# Sheet1_PCI_mez.net
KiCad netlist of a schematic drawn in Altium Designer
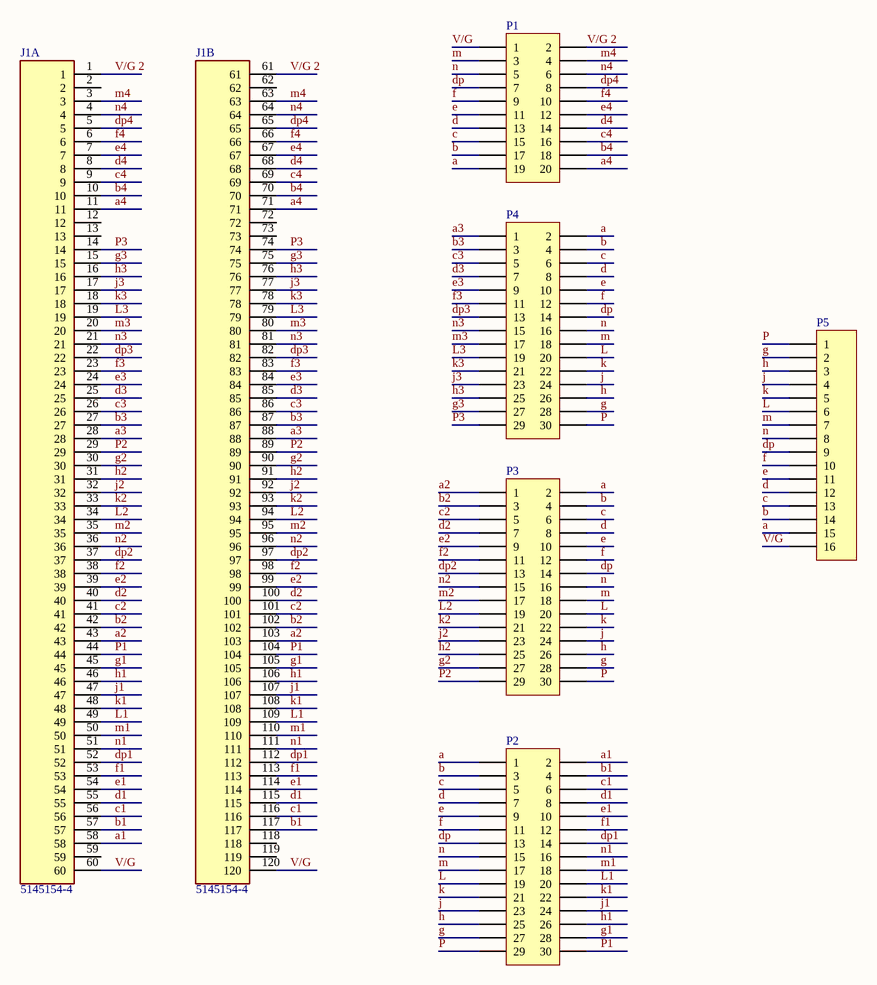
[diagram p0: Sheet1_PCI_mez.SchDoc]

(export (version "E")
  (design (tool "Eeschema 10.0.6"))
  (components
    (comp (ref "J1")
      (value "5145154-4")
      (footprint "TE_5145154-4")
      (description "Conn, Card Edge, Thermoplastic, White, 60 Dual Pos., Gold Cont., PCI ¦ TE Connectivity 5145154-4")
      (fields (field (name "MF") "TE Connectivity"))
      (libsource (lib "5145154-4") (part "5145154-4"))
    )
    (comp (ref "P1")
      (value "Header 10X2")
      (footprint "HDR2X10")
      (description "Header, 10-Pin, Dual row")
      (fields (field (name "PUBLISHER") "Altium Limited"))
      (libsource (lib "Miscellaneous Connectors") (part "Header 10X2"))
    )
    (comp (ref "P2")
      (value "Header 15X2")
      (footprint "HDR2X15")
      (description "Header, 15-Pin, Dual row")
      (fields (field (name "PUBLISHER") "Altium Limited"))
      (libsource (lib "Miscellaneous Connectors") (part "Header 15X2"))
    )
    (comp (ref "P3")
      (value "Header 15X2")
      (footprint "HDR2X15")
      (description "Header, 15-Pin, Dual row")
      (fields (field (name "PUBLISHER") "Altium Limited"))
      (libsource (lib "Miscellaneous Connectors") (part "Header 15X2"))
    )
    (comp (ref "P4")
      (value "Header 15X2")
      (footprint "HDR2X15")
      (description "Header, 15-Pin, Dual row")
      (fields (field (name "PUBLISHER") "Altium Limited"))
      (libsource (lib "Miscellaneous Connectors") (part "Header 15X2"))
    )
    (comp (ref "P5")
      (value "Header 16")
      (footprint "HDR1X16")
      (description "Header, 16-Pin")
      (fields (field (name "PUBLISHER") "Altium Limited"))
      (libsource (lib "Miscellaneous Connectors") (part "Header 16"))
    )
  )
  (nets
    (net (code "1") (name "/L") (class "Default")
      (node (ref "P2") (pin "19") (pinfunction "19_19") (pintype "passive"))
      (node (ref "P3") (pin "20") (pinfunction "20_20") (pintype "passive"))
      (node (ref "P4") (pin "20") (pinfunction "20_20") (pintype "passive"))
      (node (ref "P5") (pin "6") (pinfunction "6_6") (pintype "passive"))
    )
    (net (code "2") (name "/L1") (class "Default")
      (node (ref "J1") (pin "109") (pinfunction "109_109") (pintype "passive"))
      (node (ref "J1") (pin "49") (pinfunction "49_49") (pintype "passive"))
      (node (ref "P2") (pin "20") (pinfunction "20_20") (pintype "passive"))
    )
    (net (code "3") (name "/L2") (class "Default")
      (node (ref "J1") (pin "34") (pinfunction "34_34") (pintype "passive"))
      (node (ref "J1") (pin "94") (pinfunction "94_94") (pintype "passive"))
      (node (ref "P3") (pin "19") (pinfunction "19_19") (pintype "passive"))
    )
    (net (code "4") (name "/L3") (class "Default")
      (node (ref "J1") (pin "19") (pinfunction "19_19") (pintype "passive"))
      (node (ref "J1") (pin "79") (pinfunction "79_79") (pintype "passive"))
      (node (ref "P4") (pin "19") (pinfunction "19_19") (pintype "passive"))
    )
    (net (code "5") (name "/P") (class "Default")
      (node (ref "P2") (pin "29") (pinfunction "29_29") (pintype "passive"))
      (node (ref "P3") (pin "30") (pinfunction "30_30") (pintype "passive"))
      (node (ref "P4") (pin "30") (pinfunction "30_30") (pintype "passive"))
      (node (ref "P5") (pin "1") (pinfunction "1_1") (pintype "passive"))
    )
    (net (code "6") (name "/P1") (class "Default")
      (node (ref "J1") (pin "104") (pinfunction "104_104") (pintype "passive"))
      (node (ref "J1") (pin "44") (pinfunction "44_44") (pintype "passive"))
      (node (ref "P2") (pin "30") (pinfunction "30_30") (pintype "passive"))
    )
    (net (code "7") (name "/P2") (class "Default")
      (node (ref "J1") (pin "29") (pinfunction "29_29") (pintype "passive"))
      (node (ref "J1") (pin "89") (pinfunction "89_89") (pintype "passive"))
      (node (ref "P3") (pin "29") (pinfunction "29_29") (pintype "passive"))
    )
    (net (code "8") (name "/P3") (class "Default")
      (node (ref "J1") (pin "14") (pinfunction "14_14") (pintype "passive"))
      (node (ref "J1") (pin "74") (pinfunction "74_74") (pintype "passive"))
      (node (ref "P4") (pin "29") (pinfunction "29_29") (pintype "passive"))
    )
    (net (code "9") (name "/V{slash}G") (class "Default")
      (node (ref "J1") (pin "120") (pinfunction "120_120") (pintype "passive"))
      (node (ref "J1") (pin "60") (pinfunction "60_60") (pintype "passive"))
      (node (ref "P1") (pin "1") (pinfunction "1_1") (pintype "passive"))
      (node (ref "P5") (pin "16") (pinfunction "16_16") (pintype "passive"))
    )
    (net (code "10") (name "/V{slash}G 2") (class "Default")
      (node (ref "J1") (pin "1") (pinfunction "1_1") (pintype "passive"))
      (node (ref "J1") (pin "61") (pinfunction "61_61") (pintype "passive"))
      (node (ref "P1") (pin "2") (pinfunction "2_2") (pintype "passive"))
    )
    (net (code "11") (name "/a") (class "Default")
      (node (ref "P1") (pin "19") (pinfunction "19_19") (pintype "passive"))
      (node (ref "P2") (pin "1") (pinfunction "1_1") (pintype "passive"))
      (node (ref "P3") (pin "2") (pinfunction "2_2") (pintype "passive"))
      (node (ref "P4") (pin "2") (pinfunction "2_2") (pintype "passive"))
      (node (ref "P5") (pin "15") (pinfunction "15_15") (pintype "passive"))
    )
    (net (code "12") (name "/a1") (class "Default")
      (node (ref "J1") (pin "58") (pinfunction "58_58") (pintype "passive"))
      (node (ref "P2") (pin "2") (pinfunction "2_2") (pintype "passive"))
    )
    (net (code "13") (name "/a2") (class "Default")
      (node (ref "J1") (pin "103") (pinfunction "103_103") (pintype "passive"))
      (node (ref "J1") (pin "43") (pinfunction "43_43") (pintype "passive"))
      (node (ref "P3") (pin "1") (pinfunction "1_1") (pintype "passive"))
    )
    (net (code "14") (name "/a3") (class "Default")
      (node (ref "J1") (pin "28") (pinfunction "28_28") (pintype "passive"))
      (node (ref "J1") (pin "88") (pinfunction "88_88") (pintype "passive"))
      (node (ref "P4") (pin "1") (pinfunction "1_1") (pintype "passive"))
    )
    (net (code "15") (name "/a4") (class "Default")
      (node (ref "J1") (pin "11") (pinfunction "11_11") (pintype "passive"))
      (node (ref "J1") (pin "71") (pinfunction "71_71") (pintype "passive"))
      (node (ref "P1") (pin "20") (pinfunction "20_20") (pintype "passive"))
    )
    (net (code "16") (name "/b") (class "Default")
      (node (ref "P1") (pin "17") (pinfunction "17_17") (pintype "passive"))
      (node (ref "P2") (pin "3") (pinfunction "3_3") (pintype "passive"))
      (node (ref "P3") (pin "4") (pinfunction "4_4") (pintype "passive"))
      (node (ref "P4") (pin "4") (pinfunction "4_4") (pintype "passive"))
      (node (ref "P5") (pin "14") (pinfunction "14_14") (pintype "passive"))
    )
    (net (code "17") (name "/b1") (class "Default")
      (node (ref "J1") (pin "117") (pinfunction "117_117") (pintype "passive"))
      (node (ref "J1") (pin "57") (pinfunction "57_57") (pintype "passive"))
      (node (ref "P2") (pin "4") (pinfunction "4_4") (pintype "passive"))
    )
    (net (code "18") (name "/b2") (class "Default")
      (node (ref "J1") (pin "102") (pinfunction "102_102") (pintype "passive"))
      (node (ref "J1") (pin "42") (pinfunction "42_42") (pintype "passive"))
      (node (ref "P3") (pin "3") (pinfunction "3_3") (pintype "passive"))
    )
    (net (code "19") (name "/b3") (class "Default")
      (node (ref "J1") (pin "27") (pinfunction "27_27") (pintype "passive"))
      (node (ref "J1") (pin "87") (pinfunction "87_87") (pintype "passive"))
      (node (ref "P4") (pin "3") (pinfunction "3_3") (pintype "passive"))
    )
    (net (code "20") (name "/b4") (class "Default")
      (node (ref "J1") (pin "10") (pinfunction "10_10") (pintype "passive"))
      (node (ref "J1") (pin "70") (pinfunction "70_70") (pintype "passive"))
      (node (ref "P1") (pin "18") (pinfunction "18_18") (pintype "passive"))
    )
    (net (code "21") (name "/c") (class "Default")
      (node (ref "P1") (pin "15") (pinfunction "15_15") (pintype "passive"))
      (node (ref "P2") (pin "5") (pinfunction "5_5") (pintype "passive"))
      (node (ref "P3") (pin "6") (pinfunction "6_6") (pintype "passive"))
      (node (ref "P4") (pin "6") (pinfunction "6_6") (pintype "passive"))
      (node (ref "P5") (pin "13") (pinfunction "13_13") (pintype "passive"))
    )
    (net (code "22") (name "/c1") (class "Default")
      (node (ref "J1") (pin "116") (pinfunction "116_116") (pintype "passive"))
      (node (ref "J1") (pin "56") (pinfunction "56_56") (pintype "passive"))
      (node (ref "P2") (pin "6") (pinfunction "6_6") (pintype "passive"))
    )
    (net (code "23") (name "/c2") (class "Default")
      (node (ref "J1") (pin "101") (pinfunction "101_101") (pintype "passive"))
      (node (ref "J1") (pin "41") (pinfunction "41_41") (pintype "passive"))
      (node (ref "P3") (pin "5") (pinfunction "5_5") (pintype "passive"))
    )
    (net (code "24") (name "/c3") (class "Default")
      (node (ref "J1") (pin "26") (pinfunction "26_26") (pintype "passive"))
      (node (ref "J1") (pin "86") (pinfunction "86_86") (pintype "passive"))
      (node (ref "P4") (pin "5") (pinfunction "5_5") (pintype "passive"))
    )
    (net (code "25") (name "/c4") (class "Default")
      (node (ref "J1") (pin "69") (pinfunction "69_69") (pintype "passive"))
      (node (ref "J1") (pin "9") (pinfunction "9_9") (pintype "passive"))
      (node (ref "P1") (pin "16") (pinfunction "16_16") (pintype "passive"))
    )
    (net (code "26") (name "/d") (class "Default")
      (node (ref "P1") (pin "13") (pinfunction "13_13") (pintype "passive"))
      (node (ref "P2") (pin "7") (pinfunction "7_7") (pintype "passive"))
      (node (ref "P3") (pin "8") (pinfunction "8_8") (pintype "passive"))
      (node (ref "P4") (pin "8") (pinfunction "8_8") (pintype "passive"))
      (node (ref "P5") (pin "12") (pinfunction "12_12") (pintype "passive"))
    )
    (net (code "27") (name "/d1") (class "Default")
      (node (ref "J1") (pin "115") (pinfunction "115_115") (pintype "passive"))
      (node (ref "J1") (pin "55") (pinfunction "55_55") (pintype "passive"))
      (node (ref "P2") (pin "8") (pinfunction "8_8") (pintype "passive"))
    )
    (net (code "28") (name "/d2") (class "Default")
      (node (ref "J1") (pin "100") (pinfunction "100_100") (pintype "passive"))
      (node (ref "J1") (pin "40") (pinfunction "40_40") (pintype "passive"))
      (node (ref "P3") (pin "7") (pinfunction "7_7") (pintype "passive"))
    )
    (net (code "29") (name "/d3") (class "Default")
      (node (ref "J1") (pin "25") (pinfunction "25_25") (pintype "passive"))
      (node (ref "J1") (pin "85") (pinfunction "85_85") (pintype "passive"))
      (node (ref "P4") (pin "7") (pinfunction "7_7") (pintype "passive"))
    )
    (net (code "30") (name "/d4") (class "Default")
      (node (ref "J1") (pin "68") (pinfunction "68_68") (pintype "passive"))
      (node (ref "J1") (pin "8") (pinfunction "8_8") (pintype "passive"))
      (node (ref "P1") (pin "14") (pinfunction "14_14") (pintype "passive"))
    )
    (net (code "31") (name "/dp") (class "Default")
      (node (ref "P1") (pin "7") (pinfunction "7_7") (pintype "passive"))
      (node (ref "P2") (pin "13") (pinfunction "13_13") (pintype "passive"))
      (node (ref "P3") (pin "14") (pinfunction "14_14") (pintype "passive"))
      (node (ref "P4") (pin "14") (pinfunction "14_14") (pintype "passive"))
      (node (ref "P5") (pin "9") (pinfunction "9_9") (pintype "passive"))
    )
    (net (code "32") (name "/dp1") (class "Default")
      (node (ref "J1") (pin "112") (pinfunction "112_112") (pintype "passive"))
      (node (ref "J1") (pin "52") (pinfunction "52_52") (pintype "passive"))
      (node (ref "P2") (pin "14") (pinfunction "14_14") (pintype "passive"))
    )
    (net (code "33") (name "/dp2") (class "Default")
      (node (ref "J1") (pin "37") (pinfunction "37_37") (pintype "passive"))
      (node (ref "J1") (pin "97") (pinfunction "97_97") (pintype "passive"))
      (node (ref "P3") (pin "13") (pinfunction "13_13") (pintype "passive"))
    )
    (net (code "34") (name "/dp3") (class "Default")
      (node (ref "J1") (pin "22") (pinfunction "22_22") (pintype "passive"))
      (node (ref "J1") (pin "82") (pinfunction "82_82") (pintype "passive"))
      (node (ref "P4") (pin "13") (pinfunction "13_13") (pintype "passive"))
    )
    (net (code "35") (name "/dp4") (class "Default")
      (node (ref "J1") (pin "5") (pinfunction "5_5") (pintype "passive"))
      (node (ref "J1") (pin "65") (pinfunction "65_65") (pintype "passive"))
      (node (ref "P1") (pin "8") (pinfunction "8_8") (pintype "passive"))
    )
    (net (code "36") (name "/e") (class "Default")
      (node (ref "P1") (pin "11") (pinfunction "11_11") (pintype "passive"))
      (node (ref "P2") (pin "9") (pinfunction "9_9") (pintype "passive"))
      (node (ref "P3") (pin "10") (pinfunction "10_10") (pintype "passive"))
      (node (ref "P4") (pin "10") (pinfunction "10_10") (pintype "passive"))
      (node (ref "P5") (pin "11") (pinfunction "11_11") (pintype "passive"))
    )
    (net (code "37") (name "/e1") (class "Default")
      (node (ref "J1") (pin "114") (pinfunction "114_114") (pintype "passive"))
      (node (ref "J1") (pin "54") (pinfunction "54_54") (pintype "passive"))
      (node (ref "P2") (pin "10") (pinfunction "10_10") (pintype "passive"))
    )
    (net (code "38") (name "/e2") (class "Default")
      (node (ref "J1") (pin "39") (pinfunction "39_39") (pintype "passive"))
      (node (ref "J1") (pin "99") (pinfunction "99_99") (pintype "passive"))
      (node (ref "P3") (pin "9") (pinfunction "9_9") (pintype "passive"))
    )
    (net (code "39") (name "/e3") (class "Default")
      (node (ref "J1") (pin "24") (pinfunction "24_24") (pintype "passive"))
      (node (ref "J1") (pin "84") (pinfunction "84_84") (pintype "passive"))
      (node (ref "P4") (pin "9") (pinfunction "9_9") (pintype "passive"))
    )
    (net (code "40") (name "/e4") (class "Default")
      (node (ref "J1") (pin "67") (pinfunction "67_67") (pintype "passive"))
      (node (ref "J1") (pin "7") (pinfunction "7_7") (pintype "passive"))
      (node (ref "P1") (pin "12") (pinfunction "12_12") (pintype "passive"))
    )
    (net (code "41") (name "/f") (class "Default")
      (node (ref "P1") (pin "9") (pinfunction "9_9") (pintype "passive"))
      (node (ref "P2") (pin "11") (pinfunction "11_11") (pintype "passive"))
      (node (ref "P3") (pin "12") (pinfunction "12_12") (pintype "passive"))
      (node (ref "P4") (pin "12") (pinfunction "12_12") (pintype "passive"))
      (node (ref "P5") (pin "10") (pinfunction "10_10") (pintype "passive"))
    )
    (net (code "42") (name "/f1") (class "Default")
      (node (ref "J1") (pin "113") (pinfunction "113_113") (pintype "passive"))
      (node (ref "J1") (pin "53") (pinfunction "53_53") (pintype "passive"))
      (node (ref "P2") (pin "12") (pinfunction "12_12") (pintype "passive"))
    )
    (net (code "43") (name "/f2") (class "Default")
      (node (ref "J1") (pin "38") (pinfunction "38_38") (pintype "passive"))
      (node (ref "J1") (pin "98") (pinfunction "98_98") (pintype "passive"))
      (node (ref "P3") (pin "11") (pinfunction "11_11") (pintype "passive"))
    )
    (net (code "44") (name "/f3") (class "Default")
      (node (ref "J1") (pin "23") (pinfunction "23_23") (pintype "passive"))
      (node (ref "J1") (pin "83") (pinfunction "83_83") (pintype "passive"))
      (node (ref "P4") (pin "11") (pinfunction "11_11") (pintype "passive"))
    )
    (net (code "45") (name "/f4") (class "Default")
      (node (ref "J1") (pin "6") (pinfunction "6_6") (pintype "passive"))
      (node (ref "J1") (pin "66") (pinfunction "66_66") (pintype "passive"))
      (node (ref "P1") (pin "10") (pinfunction "10_10") (pintype "passive"))
    )
    (net (code "46") (name "/g") (class "Default")
      (node (ref "P2") (pin "27") (pinfunction "27_27") (pintype "passive"))
      (node (ref "P3") (pin "28") (pinfunction "28_28") (pintype "passive"))
      (node (ref "P4") (pin "28") (pinfunction "28_28") (pintype "passive"))
      (node (ref "P5") (pin "2") (pinfunction "2_2") (pintype "passive"))
    )
    (net (code "47") (name "/g1") (class "Default")
      (node (ref "J1") (pin "105") (pinfunction "105_105") (pintype "passive"))
      (node (ref "J1") (pin "45") (pinfunction "45_45") (pintype "passive"))
      (node (ref "P2") (pin "28") (pinfunction "28_28") (pintype "passive"))
    )
    (net (code "48") (name "/g2") (class "Default")
      (node (ref "J1") (pin "30") (pinfunction "30_30") (pintype "passive"))
      (node (ref "J1") (pin "90") (pinfunction "90_90") (pintype "passive"))
      (node (ref "P3") (pin "27") (pinfunction "27_27") (pintype "passive"))
    )
    (net (code "49") (name "/g3") (class "Default")
      (node (ref "J1") (pin "15") (pinfunction "15_15") (pintype "passive"))
      (node (ref "J1") (pin "75") (pinfunction "75_75") (pintype "passive"))
      (node (ref "P4") (pin "27") (pinfunction "27_27") (pintype "passive"))
    )
    (net (code "50") (name "/h") (class "Default")
      (node (ref "P2") (pin "25") (pinfunction "25_25") (pintype "passive"))
      (node (ref "P3") (pin "26") (pinfunction "26_26") (pintype "passive"))
      (node (ref "P4") (pin "26") (pinfunction "26_26") (pintype "passive"))
      (node (ref "P5") (pin "3") (pinfunction "3_3") (pintype "passive"))
    )
    (net (code "51") (name "/h1") (class "Default")
      (node (ref "J1") (pin "106") (pinfunction "106_106") (pintype "passive"))
      (node (ref "J1") (pin "46") (pinfunction "46_46") (pintype "passive"))
      (node (ref "P2") (pin "26") (pinfunction "26_26") (pintype "passive"))
    )
    (net (code "52") (name "/h2") (class "Default")
      (node (ref "J1") (pin "31") (pinfunction "31_31") (pintype "passive"))
      (node (ref "J1") (pin "91") (pinfunction "91_91") (pintype "passive"))
      (node (ref "P3") (pin "25") (pinfunction "25_25") (pintype "passive"))
    )
    (net (code "53") (name "/h3") (class "Default")
      (node (ref "J1") (pin "16") (pinfunction "16_16") (pintype "passive"))
      (node (ref "J1") (pin "76") (pinfunction "76_76") (pintype "passive"))
      (node (ref "P4") (pin "25") (pinfunction "25_25") (pintype "passive"))
    )
    (net (code "54") (name "/j") (class "Default")
      (node (ref "P2") (pin "23") (pinfunction "23_23") (pintype "passive"))
      (node (ref "P3") (pin "24") (pinfunction "24_24") (pintype "passive"))
      (node (ref "P4") (pin "24") (pinfunction "24_24") (pintype "passive"))
      (node (ref "P5") (pin "4") (pinfunction "4_4") (pintype "passive"))
    )
    (net (code "55") (name "/j1") (class "Default")
      (node (ref "J1") (pin "107") (pinfunction "107_107") (pintype "passive"))
      (node (ref "J1") (pin "47") (pinfunction "47_47") (pintype "passive"))
      (node (ref "P2") (pin "24") (pinfunction "24_24") (pintype "passive"))
    )
    (net (code "56") (name "/j2") (class "Default")
      (node (ref "J1") (pin "32") (pinfunction "32_32") (pintype "passive"))
      (node (ref "J1") (pin "92") (pinfunction "92_92") (pintype "passive"))
      (node (ref "P3") (pin "23") (pinfunction "23_23") (pintype "passive"))
    )
    (net (code "57") (name "/j3") (class "Default")
      (node (ref "J1") (pin "17") (pinfunction "17_17") (pintype "passive"))
      (node (ref "J1") (pin "77") (pinfunction "77_77") (pintype "passive"))
      (node (ref "P4") (pin "23") (pinfunction "23_23") (pintype "passive"))
    )
    (net (code "58") (name "/k") (class "Default")
      (node (ref "P2") (pin "21") (pinfunction "21_21") (pintype "passive"))
      (node (ref "P3") (pin "22") (pinfunction "22_22") (pintype "passive"))
      (node (ref "P4") (pin "22") (pinfunction "22_22") (pintype "passive"))
      (node (ref "P5") (pin "5") (pinfunction "5_5") (pintype "passive"))
    )
    (net (code "59") (name "/k1") (class "Default")
      (node (ref "J1") (pin "108") (pinfunction "108_108") (pintype "passive"))
      (node (ref "J1") (pin "48") (pinfunction "48_48") (pintype "passive"))
      (node (ref "P2") (pin "22") (pinfunction "22_22") (pintype "passive"))
    )
    (net (code "60") (name "/k2") (class "Default")
      (node (ref "J1") (pin "33") (pinfunction "33_33") (pintype "passive"))
      (node (ref "J1") (pin "93") (pinfunction "93_93") (pintype "passive"))
      (node (ref "P3") (pin "21") (pinfunction "21_21") (pintype "passive"))
    )
    (net (code "61") (name "/k3") (class "Default")
      (node (ref "J1") (pin "18") (pinfunction "18_18") (pintype "passive"))
      (node (ref "J1") (pin "78") (pinfunction "78_78") (pintype "passive"))
      (node (ref "P4") (pin "21") (pinfunction "21_21") (pintype "passive"))
    )
    (net (code "62") (name "/m") (class "Default")
      (node (ref "P1") (pin "3") (pinfunction "3_3") (pintype "passive"))
      (node (ref "P2") (pin "17") (pinfunction "17_17") (pintype "passive"))
      (node (ref "P3") (pin "18") (pinfunction "18_18") (pintype "passive"))
      (node (ref "P4") (pin "18") (pinfunction "18_18") (pintype "passive"))
      (node (ref "P5") (pin "7") (pinfunction "7_7") (pintype "passive"))
    )
    (net (code "63") (name "/m1") (class "Default")
      (node (ref "J1") (pin "110") (pinfunction "110_110") (pintype "passive"))
      (node (ref "J1") (pin "50") (pinfunction "50_50") (pintype "passive"))
      (node (ref "P2") (pin "18") (pinfunction "18_18") (pintype "passive"))
    )
    (net (code "64") (name "/m2") (class "Default")
      (node (ref "J1") (pin "35") (pinfunction "35_35") (pintype "passive"))
      (node (ref "J1") (pin "95") (pinfunction "95_95") (pintype "passive"))
      (node (ref "P3") (pin "17") (pinfunction "17_17") (pintype "passive"))
    )
    (net (code "65") (name "/m3") (class "Default")
      (node (ref "J1") (pin "20") (pinfunction "20_20") (pintype "passive"))
      (node (ref "J1") (pin "80") (pinfunction "80_80") (pintype "passive"))
      (node (ref "P4") (pin "17") (pinfunction "17_17") (pintype "passive"))
    )
    (net (code "66") (name "/m4") (class "Default")
      (node (ref "J1") (pin "3") (pinfunction "3_3") (pintype "passive"))
      (node (ref "J1") (pin "63") (pinfunction "63_63") (pintype "passive"))
      (node (ref "P1") (pin "4") (pinfunction "4_4") (pintype "passive"))
    )
    (net (code "67") (name "/n") (class "Default")
      (node (ref "P1") (pin "5") (pinfunction "5_5") (pintype "passive"))
      (node (ref "P2") (pin "15") (pinfunction "15_15") (pintype "passive"))
      (node (ref "P3") (pin "16") (pinfunction "16_16") (pintype "passive"))
      (node (ref "P4") (pin "16") (pinfunction "16_16") (pintype "passive"))
      (node (ref "P5") (pin "8") (pinfunction "8_8") (pintype "passive"))
    )
    (net (code "68") (name "/n1") (class "Default")
      (node (ref "J1") (pin "111") (pinfunction "111_111") (pintype "passive"))
      (node (ref "J1") (pin "51") (pinfunction "51_51") (pintype "passive"))
      (node (ref "P2") (pin "16") (pinfunction "16_16") (pintype "passive"))
    )
    (net (code "69") (name "/n2") (class "Default")
      (node (ref "J1") (pin "36") (pinfunction "36_36") (pintype "passive"))
      (node (ref "J1") (pin "96") (pinfunction "96_96") (pintype "passive"))
      (node (ref "P3") (pin "15") (pinfunction "15_15") (pintype "passive"))
    )
    (net (code "70") (name "/n3") (class "Default")
      (node (ref "J1") (pin "21") (pinfunction "21_21") (pintype "passive"))
      (node (ref "J1") (pin "81") (pinfunction "81_81") (pintype "passive"))
      (node (ref "P4") (pin "15") (pinfunction "15_15") (pintype "passive"))
    )
    (net (code "71") (name "/n4") (class "Default")
      (node (ref "J1") (pin "4") (pinfunction "4_4") (pintype "passive"))
      (node (ref "J1") (pin "64") (pinfunction "64_64") (pintype "passive"))
      (node (ref "P1") (pin "6") (pinfunction "6_6") (pintype "passive"))
    )
    (net (code "72") (name "unconnected-(J1-Pad2)") (class "Default")
      (node (ref "J1") (pin "2") (pinfunction "2_2") (pintype "passive"))
    )
    (net (code "73") (name "unconnected-(J1-Pad12)") (class "Default")
      (node (ref "J1") (pin "12") (pinfunction "12_12") (pintype "passive"))
    )
    (net (code "74") (name "unconnected-(J1-Pad13)") (class "Default")
      (node (ref "J1") (pin "13") (pinfunction "13_13") (pintype "passive"))
    )
    (net (code "75") (name "unconnected-(J1-Pad59)") (class "Default")
      (node (ref "J1") (pin "59") (pinfunction "59_59") (pintype "passive"))
    )
    (net (code "76") (name "unconnected-(J1-Pad62)") (class "Default")
      (node (ref "J1") (pin "62") (pinfunction "62_62") (pintype "passive"))
    )
    (net (code "77") (name "unconnected-(J1-Pad72)") (class "Default")
      (node (ref "J1") (pin "72") (pinfunction "72_72") (pintype "passive"))
    )
    (net (code "78") (name "unconnected-(J1-Pad73)") (class "Default")
      (node (ref "J1") (pin "73") (pinfunction "73_73") (pintype "passive"))
    )
    (net (code "79") (name "unconnected-(J1-Pad118)") (class "Default")
      (node (ref "J1") (pin "118") (pinfunction "118_118") (pintype "passive"))
    )
    (net (code "80") (name "unconnected-(J1-Pad119)") (class "Default")
      (node (ref "J1") (pin "119") (pinfunction "119_119") (pintype "passive"))
    )
  )
)
